# berimbau.net
KiCad netlist of a schematic drawn in EAGLE
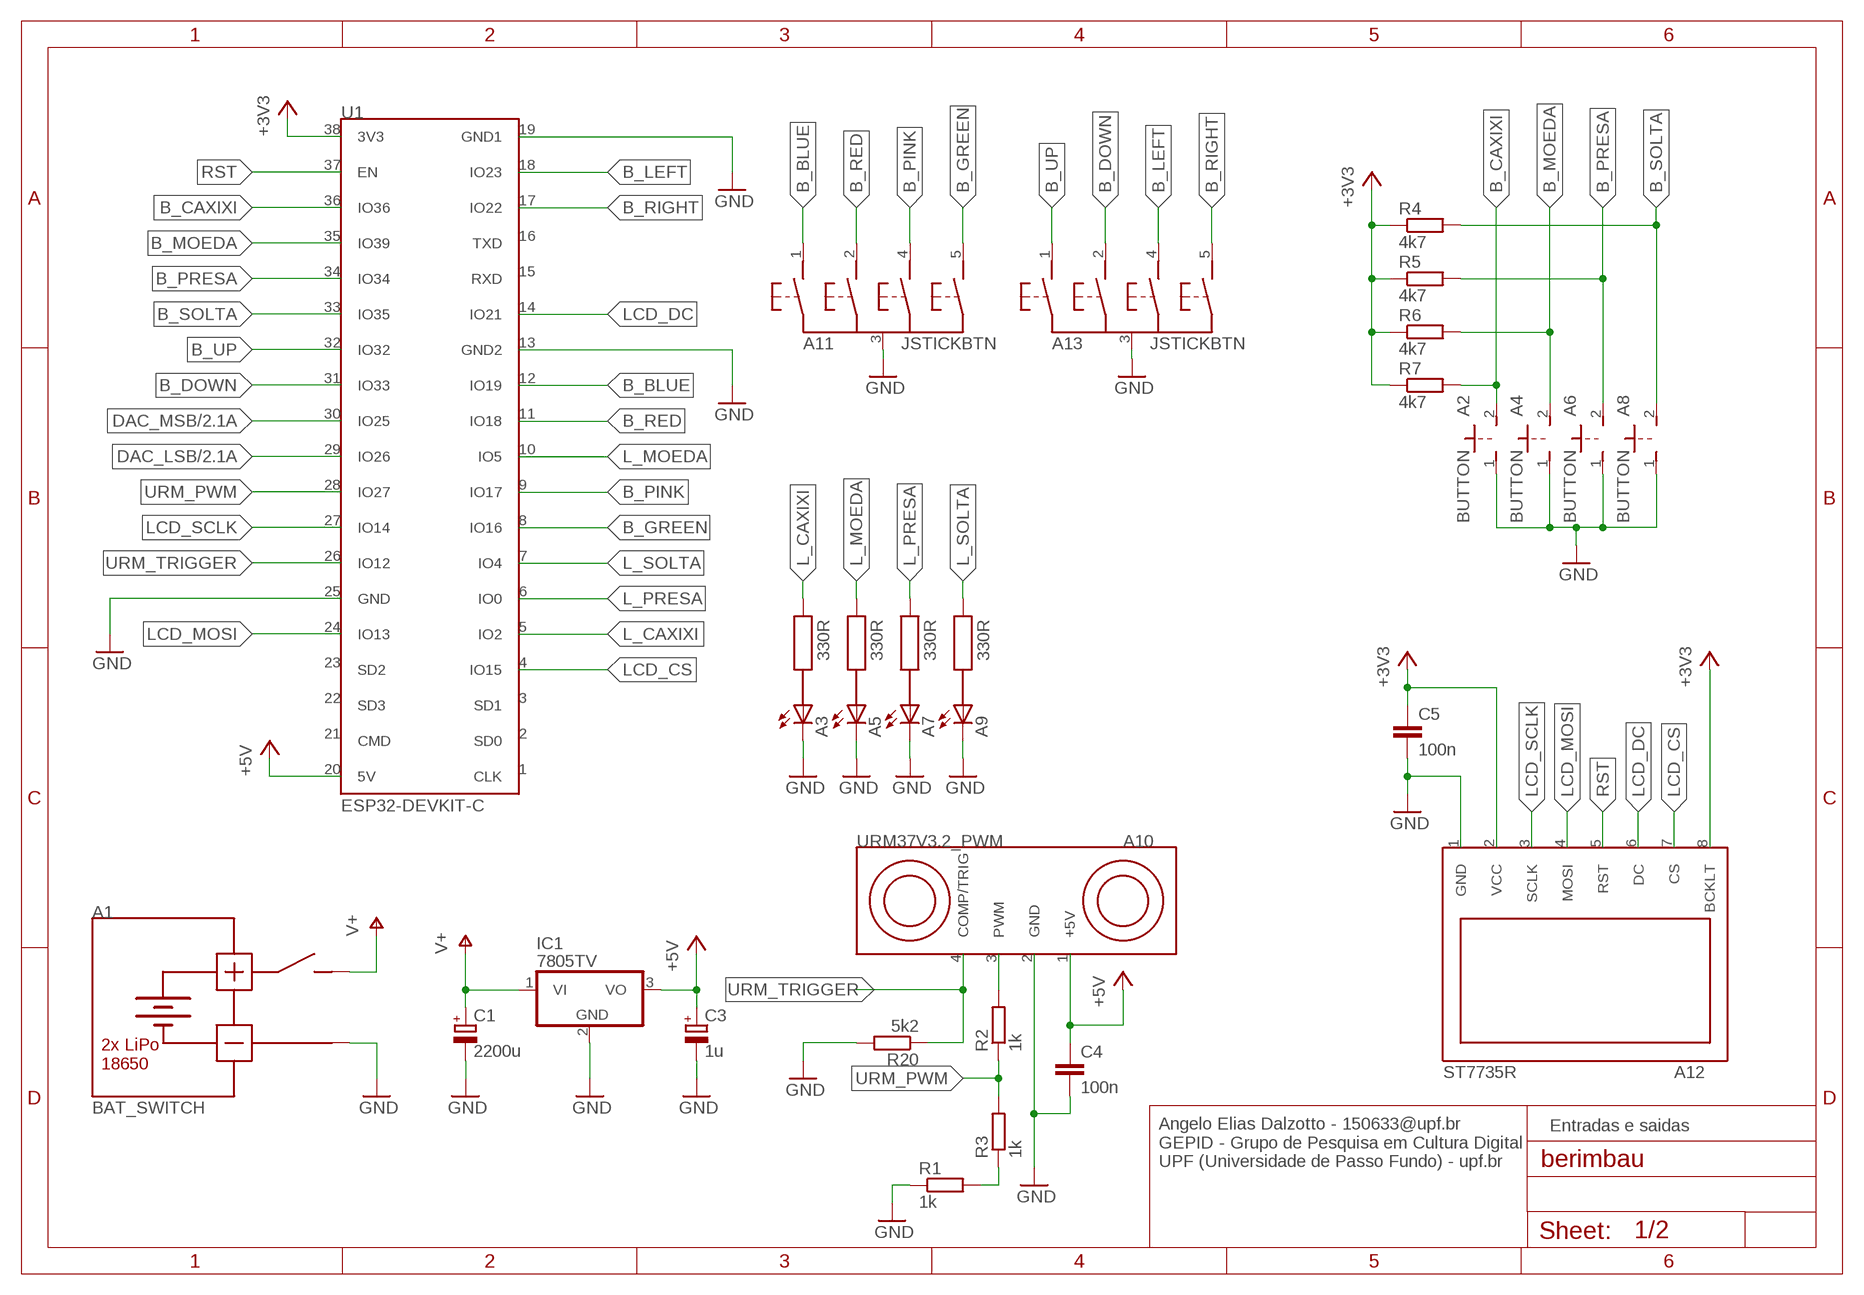
[diagram p0: schematic, sheet 1]
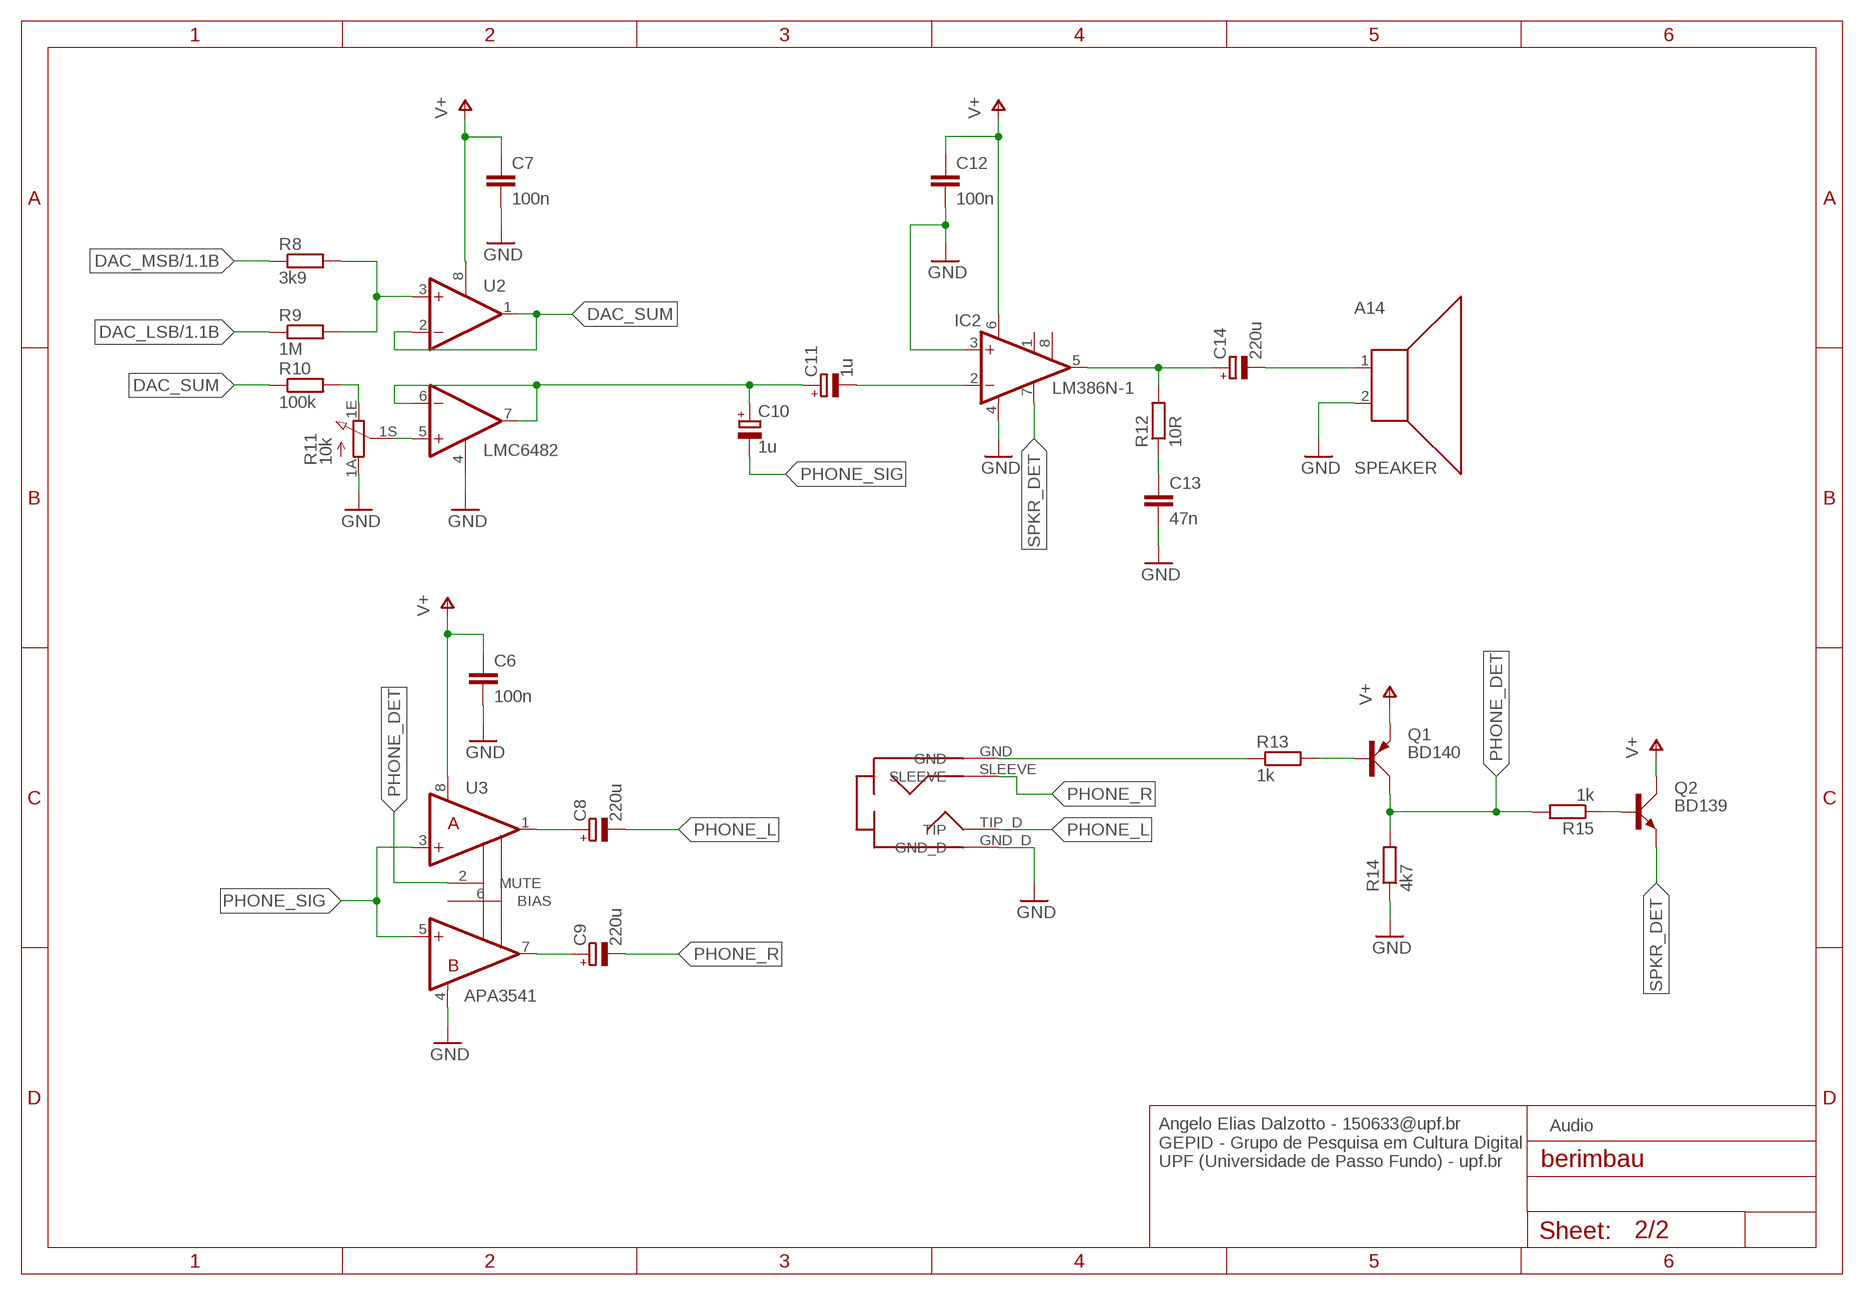
[diagram p1: schematic, sheet 2]

(export (version "E")
  (design (tool "Eeschema 10.0.6"))
  (components
    (comp (ref "A1")
      (value "BAT_SWITCH")
      (footprint "eagle-import:1X02")
      (libsource (lib "eagle-import") (part "BAT_SWITCH"))
    )
    (comp (ref "A2")
      (value "BUTTON")
      (footprint "eagle-import:1X02")
      (libsource (lib "eagle-import") (part "BUTTON"))
    )
    (comp (ref "A3")
      (value "LED")
      (footprint "eagle-import:1X02")
      (libsource (lib "eagle-import") (part "LED"))
    )
    (comp (ref "A4")
      (value "BUTTON")
      (footprint "eagle-import:1X02")
      (libsource (lib "eagle-import") (part "BUTTON"))
    )
    (comp (ref "A5")
      (value "LED")
      (footprint "eagle-import:1X02")
      (libsource (lib "eagle-import") (part "LED"))
    )
    (comp (ref "A6")
      (value "BUTTON")
      (footprint "eagle-import:1X02")
      (libsource (lib "eagle-import") (part "BUTTON"))
    )
    (comp (ref "A7")
      (value "LED")
      (footprint "eagle-import:1X02")
      (libsource (lib "eagle-import") (part "LED"))
    )
    (comp (ref "A8")
      (value "BUTTON")
      (footprint "eagle-import:1X02")
      (libsource (lib "eagle-import") (part "BUTTON"))
    )
    (comp (ref "A9")
      (value "LED")
      (footprint "eagle-import:1X02")
      (libsource (lib "eagle-import") (part "LED"))
    )
    (comp (ref "A10")
      (value "URM37V3.2_PWM")
      (footprint "eagle-import:1X04")
      (libsource (lib "eagle-import") (part "URM37V3.2_PWM"))
    )
    (comp (ref "A11")
      (value "JSTICKBTN")
      (footprint "eagle-import:1X05")
      (libsource (lib "eagle-import") (part "JSTICKBTN"))
    )
    (comp (ref "A12")
      (value "ST7735R")
      (footprint "eagle-import:1X08")
      (libsource (lib "eagle-import") (part "ST7735R"))
    )
    (comp (ref "A13")
      (value "JSTICKBTN")
      (footprint "eagle-import:1X05")
      (libsource (lib "eagle-import") (part "JSTICKBTN"))
    )
    (comp (ref "C1")
      (value "2200u")
      (footprint "eagle-import:E3,5-10")
      (libsource (lib "eagle-import") (part "CPOL-EUE3.5-10"))
    )
    (comp (ref "C3")
      (value "1u")
      (footprint "eagle-import:E2-5")
      (libsource (lib "eagle-import") (part "CPOL-EUE2-5"))
    )
    (comp (ref "C4")
      (value "100n")
      (footprint "eagle-import:C050-030X075")
      (libsource (lib "eagle-import") (part "C-EU050-030X075"))
    )
    (comp (ref "C5")
      (value "100n")
      (footprint "eagle-import:C050-030X075")
      (libsource (lib "eagle-import") (part "C-EU050-030X075"))
    )
    (comp (ref "IC1")
      (value "7805TV")
      (footprint "eagle-import:TO220V")
      (libsource (lib "eagle-import") (part "78TV05"))
    )
    (comp (ref "R1")
      (value "1k")
      (footprint "eagle-import:0207_10")
      (libsource (lib "eagle-import") (part "R-EU_0207/10"))
    )
    (comp (ref "R2")
      (value "1k")
      (footprint "eagle-import:0207_10")
      (libsource (lib "eagle-import") (part "R-EU_0207/10"))
    )
    (comp (ref "R3")
      (value "1k")
      (footprint "eagle-import:0207_10")
      (libsource (lib "eagle-import") (part "R-EU_0207/10"))
    )
    (comp (ref "R4")
      (value "4k7")
      (footprint "eagle-import:0207_10")
      (libsource (lib "eagle-import") (part "R-EU_0207/10"))
    )
    (comp (ref "R5")
      (value "4k7")
      (footprint "eagle-import:0207_10")
      (libsource (lib "eagle-import") (part "R-EU_0207/10"))
    )
    (comp (ref "R6")
      (value "4k7")
      (footprint "eagle-import:0207_10")
      (libsource (lib "eagle-import") (part "R-EU_0207/10"))
    )
    (comp (ref "R7")
      (value "4k7")
      (footprint "eagle-import:0207_10")
      (libsource (lib "eagle-import") (part "R-EU_0207/10"))
    )
    (comp (ref "R20")
      (value "5k2")
      (footprint "eagle-import:0207_10")
      (libsource (lib "eagle-import") (part "R-EU_0207/10"))
    )
    (comp (ref "U1")
      (value "ESP32-DEVKIT-C")
      (footprint "eagle-import:ESP32")
      (libsource (lib "eagle-import") (part "ESP32-DEVKIT-C"))
    )
    (comp (ref "A14")
      (value "SPEAKER")
      (footprint "eagle-import:1X02")
      (libsource (lib "eagle-import") (part "SPEAKER"))
    )
    (comp (ref "C6")
      (value "100n")
      (footprint "eagle-import:C050-030X075")
      (libsource (lib "eagle-import") (part "C-EU050-030X075"))
    )
    (comp (ref "C7")
      (value "100n")
      (footprint "eagle-import:C050-030X075")
      (libsource (lib "eagle-import") (part "C-EU050-030X075"))
    )
    (comp (ref "C8")
      (value "220u")
      (footprint "eagle-import:E2-5")
      (libsource (lib "eagle-import") (part "CPOL-EUE2-5"))
    )
    (comp (ref "C9")
      (value "220u")
      (footprint "eagle-import:E2-5")
      (libsource (lib "eagle-import") (part "CPOL-EUE2-5"))
    )
    (comp (ref "C10")
      (value "1u")
      (footprint "eagle-import:E2-5")
      (libsource (lib "eagle-import") (part "CPOL-EUE2-5"))
    )
    (comp (ref "C11")
      (value "1u")
      (footprint "eagle-import:E2-5")
      (libsource (lib "eagle-import") (part "CPOL-EUE2-5"))
    )
    (comp (ref "C12")
      (value "100n")
      (footprint "eagle-import:C050-030X075")
      (libsource (lib "eagle-import") (part "C-EU050-030X075"))
    )
    (comp (ref "C13")
      (value "47n")
      (footprint "eagle-import:C050-030X075")
      (libsource (lib "eagle-import") (part "C-EU050-030X075"))
    )
    (comp (ref "C14")
      (value "220u")
      (footprint "eagle-import:E3,5-10")
      (libsource (lib "eagle-import") (part "CPOL-EUE3.5-10"))
    )
    (comp (ref "IC2")
      (value "LM386N-1")
      (footprint "eagle-import:DIL08")
      (libsource (lib "eagle-import") (part "LM386?-N1"))
    )
    (comp (ref "J1")
      (value "P2_RPI")
      (footprint "eagle-import:P2_RASPI")
      (libsource (lib "eagle-import") (part "P2_RPI"))
    )
    (comp (ref "Q1")
      (value "BD140")
      (footprint "eagle-import:TO126AV")
      (libsource (lib "eagle-import") (part "BD140"))
    )
    (comp (ref "Q2")
      (value "BD139")
      (footprint "eagle-import:TO126AV")
      (libsource (lib "eagle-import") (part "BD139"))
    )
    (comp (ref "R8")
      (value "3k9")
      (footprint "eagle-import:0207_10")
      (libsource (lib "eagle-import") (part "R-EU_0207/10"))
    )
    (comp (ref "R9")
      (value "1M")
      (footprint "eagle-import:0207_10")
      (libsource (lib "eagle-import") (part "R-EU_0207/10"))
    )
    (comp (ref "R10")
      (value "100k")
      (footprint "eagle-import:0207_10")
      (libsource (lib "eagle-import") (part "R-EU_0207/10"))
    )
    (comp (ref "R11")
      (value "10k")
      (footprint "eagle-import:PC16S")
      (libsource (lib "eagle-import") (part "POT_SMALL"))
    )
    (comp (ref "R12")
      (value "10R")
      (footprint "eagle-import:0207_10")
      (libsource (lib "eagle-import") (part "R-EU_0207/10"))
    )
    (comp (ref "R13")
      (value "1k")
      (footprint "eagle-import:0207_10")
      (libsource (lib "eagle-import") (part "R-EU_0207/10"))
    )
    (comp (ref "R14")
      (value "4k7")
      (footprint "eagle-import:0207_10")
      (libsource (lib "eagle-import") (part "R-EU_0207/10"))
    )
    (comp (ref "R15")
      (value "1k")
      (footprint "eagle-import:0207_10")
      (libsource (lib "eagle-import") (part "R-EU_0207/10"))
    )
    (comp (ref "U2")
      (value "LMC6482")
      (footprint "eagle-import:DIL08")
      (libsource (lib "eagle-import") (part "LMC6482"))
    )
    (comp (ref "U3")
      (value "APA3541")
      (footprint "eagle-import:DIL08")
      (libsource (lib "eagle-import") (part "APA3541"))
    )
  )
  (nets
    (net (code "1") (name "+3V3") (class "Default")
      (node (ref "A12") (pin "2") (pinfunction "VCC_2") (pintype "power_in"))
      (node (ref "A12") (pin "8") (pinfunction "BCKLT_8") (pintype "input"))
      (node (ref "C5") (pin "1") (pinfunction "1_1") (pintype "passive"))
      (node (ref "R4") (pin "1") (pinfunction "1_1") (pintype "passive"))
      (node (ref "R5") (pin "1") (pinfunction "1_1") (pintype "passive"))
      (node (ref "R6") (pin "1") (pinfunction "1_1") (pintype "passive"))
      (node (ref "R7") (pin "1") (pinfunction "1_1") (pintype "passive"))
      (node (ref "U1") (pin "38") (pinfunction "3V3_38") (pintype "power_in"))
    )
    (net (code "2") (name "+5V") (class "Default")
      (node (ref "A10") (pin "1") (pinfunction "+5V_1") (pintype "power_in"))
      (node (ref "C3") (pin "+") (pinfunction "+_+") (pintype "passive"))
      (node (ref "C4") (pin "1") (pinfunction "1_1") (pintype "passive"))
      (node (ref "IC1") (pin "3") (pinfunction "VO_3") (pintype "passive"))
      (node (ref "U1") (pin "20") (pinfunction "5V_20") (pintype "power_in"))
    )
    (net (code "3") (name "B_BLUE") (class "Default")
      (node (ref "A11") (pin "1") (pinfunction "B1_1") (pintype "passive"))
      (node (ref "U1") (pin "12") (pinfunction "IO19_12") (pintype "bidirectional"))
    )
    (net (code "4") (name "B_CAXIXI") (class "Default")
      (node (ref "A2") (pin "2") (pinfunction "S_2") (pintype "passive"))
      (node (ref "R7") (pin "2") (pinfunction "2_2") (pintype "passive"))
      (node (ref "U1") (pin "36") (pinfunction "IO36_36") (pintype "input"))
    )
    (net (code "5") (name "B_DOWN") (class "Default")
      (node (ref "A13") (pin "2") (pinfunction "B2_2") (pintype "passive"))
      (node (ref "U1") (pin "31") (pinfunction "IO33_31") (pintype "bidirectional"))
    )
    (net (code "6") (name "B_GREEN") (class "Default")
      (node (ref "A11") (pin "5") (pinfunction "B4_5") (pintype "passive"))
      (node (ref "U1") (pin "8") (pinfunction "IO16_8") (pintype "bidirectional"))
    )
    (net (code "7") (name "B_LEFT") (class "Default")
      (node (ref "A13") (pin "4") (pinfunction "B3_4") (pintype "passive"))
      (node (ref "U1") (pin "18") (pinfunction "IO23_18") (pintype "bidirectional"))
    )
    (net (code "8") (name "B_MOEDA") (class "Default")
      (node (ref "A4") (pin "2") (pinfunction "S_2") (pintype "passive"))
      (node (ref "R6") (pin "2") (pinfunction "2_2") (pintype "passive"))
      (node (ref "U1") (pin "35") (pinfunction "IO39_35") (pintype "input"))
    )
    (net (code "9") (name "B_PINK") (class "Default")
      (node (ref "A11") (pin "4") (pinfunction "B3_4") (pintype "passive"))
      (node (ref "U1") (pin "9") (pinfunction "IO17_9") (pintype "bidirectional"))
    )
    (net (code "10") (name "B_PRESA") (class "Default")
      (node (ref "A6") (pin "2") (pinfunction "S_2") (pintype "passive"))
      (node (ref "R5") (pin "2") (pinfunction "2_2") (pintype "passive"))
      (node (ref "U1") (pin "34") (pinfunction "IO34_34") (pintype "input"))
    )
    (net (code "11") (name "B_RED") (class "Default")
      (node (ref "A11") (pin "2") (pinfunction "B2_2") (pintype "passive"))
      (node (ref "U1") (pin "11") (pinfunction "IO18_11") (pintype "bidirectional"))
    )
    (net (code "12") (name "B_RIGHT") (class "Default")
      (node (ref "A13") (pin "5") (pinfunction "B4_5") (pintype "passive"))
      (node (ref "U1") (pin "17") (pinfunction "IO22_17") (pintype "bidirectional"))
    )
    (net (code "13") (name "B_SOLTA") (class "Default")
      (node (ref "A8") (pin "2") (pinfunction "S_2") (pintype "passive"))
      (node (ref "R4") (pin "2") (pinfunction "2_2") (pintype "passive"))
      (node (ref "U1") (pin "33") (pinfunction "IO35_33") (pintype "input"))
    )
    (net (code "14") (name "B_UP") (class "Default")
      (node (ref "A13") (pin "1") (pinfunction "B1_1") (pintype "passive"))
      (node (ref "U1") (pin "32") (pinfunction "IO32_32") (pintype "bidirectional"))
    )
    (net (code "15") (name "DAC_LSB") (class "Default")
      (node (ref "R9") (pin "1") (pinfunction "1_1") (pintype "passive"))
      (node (ref "U1") (pin "29") (pinfunction "IO26_29") (pintype "bidirectional"))
    )
    (net (code "16") (name "DAC_MSB") (class "Default")
      (node (ref "R8") (pin "1") (pinfunction "1_1") (pintype "passive"))
      (node (ref "U1") (pin "30") (pinfunction "IO25_30") (pintype "bidirectional"))
    )
    (net (code "17") (name "DAC_SUM") (class "Default")
      (node (ref "R10") (pin "1") (pinfunction "1_1") (pintype "passive"))
      (node (ref "U2") (pin "1") (pinfunction "OUT_A_1") (pintype "output"))
      (node (ref "U2") (pin "2") (pinfunction "-IN_A_2") (pintype "input"))
    )
    (net (code "18") (name "GND") (class "Default")
      (node (ref "A1") (pin "2") (pinfunction "-_2") (pintype "power_in"))
      (node (ref "A10") (pin "2") (pinfunction "GND_2") (pintype "power_in"))
      (node (ref "A11") (pin "3") (pinfunction "COM_3") (pintype "passive"))
      (node (ref "A12") (pin "1") (pinfunction "GND_1") (pintype "power_in"))
      (node (ref "A13") (pin "3") (pinfunction "COM_3") (pintype "passive"))
      (node (ref "A14") (pin "2") (pinfunction "-_2") (pintype "passive"))
      (node (ref "A2") (pin "1") (pinfunction "P_1") (pintype "passive"))
      (node (ref "A3") (pin "2") (pinfunction "C_2") (pintype "passive"))
      (node (ref "A4") (pin "1") (pinfunction "P_1") (pintype "passive"))
      (node (ref "A5") (pin "2") (pinfunction "C_2") (pintype "passive"))
      (node (ref "A6") (pin "1") (pinfunction "P_1") (pintype "passive"))
      (node (ref "A7") (pin "2") (pinfunction "C_2") (pintype "passive"))
      (node (ref "A8") (pin "1") (pinfunction "P_1") (pintype "passive"))
      (node (ref "A9") (pin "2") (pinfunction "C_2") (pintype "passive"))
      (node (ref "C1") (pin "-") (pinfunction "-_-") (pintype "passive"))
      (node (ref "C12") (pin "2") (pinfunction "2_2") (pintype "passive"))
      (node (ref "C13") (pin "2") (pinfunction "2_2") (pintype "passive"))
      (node (ref "C3") (pin "-") (pinfunction "-_-") (pintype "passive"))
      (node (ref "C4") (pin "2") (pinfunction "2_2") (pintype "passive"))
      (node (ref "C5") (pin "2") (pinfunction "2_2") (pintype "passive"))
      (node (ref "C6") (pin "2") (pinfunction "2_2") (pintype "passive"))
      (node (ref "C7") (pin "2") (pinfunction "2_2") (pintype "passive"))
      (node (ref "IC1") (pin "2") (pinfunction "GND_2") (pintype "passive"))
      (node (ref "IC2") (pin "3") (pinfunction "+IN_3") (pintype "input"))
      (node (ref "IC2") (pin "4") (pinfunction "GND_4") (pintype "power_in"))
      (node (ref "J1") (pin "GND_D") (pinfunction "GND_D_GND_D") (pintype "bidirectional"))
      (node (ref "R1") (pin "1") (pinfunction "1_1") (pintype "passive"))
      (node (ref "R11") (pin "1A") (pinfunction "A_1A") (pintype "passive"))
      (node (ref "R14") (pin "1") (pinfunction "1_1") (pintype "passive"))
      (node (ref "R20") (pin "2") (pinfunction "2_2") (pintype "passive"))
      (node (ref "U1") (pin "13") (pinfunction "GND2_13") (pintype "power_in"))
      (node (ref "U1") (pin "19") (pinfunction "GND1_19") (pintype "power_in"))
      (node (ref "U1") (pin "25") (pinfunction "GND_25") (pintype "power_in"))
      (node (ref "U2") (pin "4") (pinfunction "V-_4") (pintype "power_in"))
      (node (ref "U3") (pin "4") (pinfunction "GND_4") (pintype "power_in"))
    )
    (net (code "19") (name "LCD_CS") (class "Default")
      (node (ref "A12") (pin "7") (pinfunction "CS_7") (pintype "input"))
      (node (ref "U1") (pin "4") (pinfunction "IO15_4") (pintype "output"))
    )
    (net (code "20") (name "LCD_DC") (class "Default")
      (node (ref "A12") (pin "6") (pinfunction "DC_6") (pintype "input"))
      (node (ref "U1") (pin "14") (pinfunction "IO21_14") (pintype "bidirectional"))
    )
    (net (code "21") (name "LCD_MOSI") (class "Default")
      (node (ref "A12") (pin "4") (pinfunction "MOSI_4") (pintype "input"))
      (node (ref "U1") (pin "24") (pinfunction "IO13_24") (pintype "bidirectional"))
    )
    (net (code "22") (name "LCD_SCLK") (class "Default")
      (node (ref "A12") (pin "3") (pinfunction "SCLK_3") (pintype "input"))
      (node (ref "U1") (pin "27") (pinfunction "IO14_27") (pintype "bidirectional"))
    )
    (net (code "23") (name "L_CAXIXI") (class "Default")
      (node (ref "A3") (pin "1") (pinfunction "A_1") (pintype "passive"))
      (node (ref "U1") (pin "5") (pinfunction "IO2_5") (pintype "output"))
    )
    (net (code "24") (name "L_MOEDA") (class "Default")
      (node (ref "A5") (pin "1") (pinfunction "A_1") (pintype "passive"))
      (node (ref "U1") (pin "10") (pinfunction "IO5_10") (pintype "output"))
    )
    (net (code "25") (name "L_PRESA") (class "Default")
      (node (ref "A7") (pin "1") (pinfunction "A_1") (pintype "passive"))
      (node (ref "U1") (pin "6") (pinfunction "IO0_6") (pintype "output"))
    )
    (net (code "26") (name "L_SOLTA") (class "Default")
      (node (ref "A9") (pin "1") (pinfunction "A_1") (pintype "passive"))
      (node (ref "U1") (pin "7") (pinfunction "IO4_7") (pintype "output"))
    )
    (net (code "27") (name "Net-(A10-PWM)") (class "Default")
      (node (ref "A10") (pin "3") (pinfunction "PWM_3") (pintype "output"))
      (node (ref "R2") (pin "2") (pinfunction "2_2") (pintype "passive"))
    )
    (net (code "28") (name "Net-(A14-+)") (class "Default")
      (node (ref "A14") (pin "1") (pinfunction "+_1") (pintype "passive"))
      (node (ref "C14") (pin "-") (pinfunction "-_-") (pintype "passive"))
    )
    (net (code "29") (name "Net-(C13-Pad1)") (class "Default")
      (node (ref "C13") (pin "1") (pinfunction "1_1") (pintype "passive"))
      (node (ref "R12") (pin "1") (pinfunction "1_1") (pintype "passive"))
    )
    (net (code "30") (name "Net-(IC2--IN)") (class "Default")
      (node (ref "C11") (pin "-") (pinfunction "-_-") (pintype "passive"))
      (node (ref "IC2") (pin "2") (pinfunction "-IN_2") (pintype "input"))
    )
    (net (code "31") (name "Net-(IC2-OUT)") (class "Default")
      (node (ref "C14") (pin "+") (pinfunction "+_+") (pintype "passive"))
      (node (ref "IC2") (pin "5") (pinfunction "OUT_5") (pintype "output"))
      (node (ref "R12") (pin "2") (pinfunction "2_2") (pintype "passive"))
    )
    (net (code "32") (name "Net-(J1-PadGND)") (class "Default")
      (node (ref "J1") (pin "GND") (pinfunction "GND_GND") (pintype "bidirectional"))
      (node (ref "R13") (pin "1") (pinfunction "1_1") (pintype "passive"))
    )
    (net (code "33") (name "Net-(Q1-PadB)") (class "Default")
      (node (ref "Q1") (pin "B") (pinfunction "B_B") (pintype "passive"))
      (node (ref "R13") (pin "2") (pinfunction "2_2") (pintype "passive"))
    )
    (net (code "34") (name "Net-(Q2-PadB)") (class "Default")
      (node (ref "Q2") (pin "B") (pinfunction "B_B") (pintype "passive"))
      (node (ref "R15") (pin "1") (pinfunction "1_1") (pintype "passive"))
    )
    (net (code "35") (name "Net-(R1-Pad2)") (class "Default")
      (node (ref "R1") (pin "2") (pinfunction "2_2") (pintype "passive"))
      (node (ref "R3") (pin "1") (pinfunction "1_1") (pintype "passive"))
    )
    (net (code "36") (name "Net-(R11-E)") (class "Default")
      (node (ref "R10") (pin "2") (pinfunction "2_2") (pintype "passive"))
      (node (ref "R11") (pin "1E") (pinfunction "E_1E") (pintype "passive"))
    )
    (net (code "37") (name "Net-(R11-S)") (class "Default")
      (node (ref "R11") (pin "1S") (pinfunction "S_1S") (pintype "passive"))
      (node (ref "U2") (pin "5") (pinfunction "+IN_B_5") (pintype "input"))
    )
    (net (code "38") (name "Net-(U2-+IN_A)") (class "Default")
      (node (ref "R8") (pin "2") (pinfunction "2_2") (pintype "passive"))
      (node (ref "R9") (pin "2") (pinfunction "2_2") (pintype "passive"))
      (node (ref "U2") (pin "3") (pinfunction "+IN_A_3") (pintype "input"))
    )
    (net (code "39") (name "Net-(U2--IN_B)") (class "Default")
      (node (ref "C10") (pin "+") (pinfunction "+_+") (pintype "passive"))
      (node (ref "C11") (pin "+") (pinfunction "+_+") (pintype "passive"))
      (node (ref "U2") (pin "6") (pinfunction "-IN_B_6") (pintype "input"))
      (node (ref "U2") (pin "7") (pinfunction "OUT_B_7") (pintype "output"))
    )
    (net (code "40") (name "Net-(U3-OUT_A)") (class "Default")
      (node (ref "C8") (pin "+") (pinfunction "+_+") (pintype "passive"))
      (node (ref "U3") (pin "1") (pinfunction "OUT_A_1") (pintype "output"))
    )
    (net (code "41") (name "Net-(U3-OUT_B)") (class "Default")
      (node (ref "C9") (pin "+") (pinfunction "+_+") (pintype "passive"))
      (node (ref "U3") (pin "7") (pinfunction "OUT_B_7") (pintype "output"))
    )
    (net (code "42") (name "PHONE_DET") (class "Default")
      (node (ref "Q1") (pin "C") (pinfunction "C_C") (pintype "passive"))
      (node (ref "R14") (pin "2") (pinfunction "2_2") (pintype "passive"))
      (node (ref "R15") (pin "2") (pinfunction "2_2") (pintype "passive"))
      (node (ref "U3") (pin "2") (pinfunction "MUTE_2") (pintype "input"))
    )
    (net (code "43") (name "PHONE_L") (class "Default")
      (node (ref "C8") (pin "-") (pinfunction "-_-") (pintype "passive"))
      (node (ref "J1") (pin "TIP_D") (pinfunction "TIP_TIP_D") (pintype "bidirectional"))
    )
    (net (code "44") (name "PHONE_R") (class "Default")
      (node (ref "C9") (pin "-") (pinfunction "-_-") (pintype "passive"))
      (node (ref "J1") (pin "SLEEVE") (pinfunction "SLEEVE_SLEEVE") (pintype "bidirectional"))
    )
    (net (code "45") (name "PHONE_SIG") (class "Default")
      (node (ref "C10") (pin "-") (pinfunction "-_-") (pintype "passive"))
      (node (ref "U3") (pin "3") (pinfunction "+IN_A_3") (pintype "input"))
      (node (ref "U3") (pin "5") (pinfunction "+IN_B_5") (pintype "input"))
    )
    (net (code "46") (name "RST") (class "Default")
      (node (ref "A12") (pin "5") (pinfunction "RST_5") (pintype "input"))
      (node (ref "U1") (pin "37") (pinfunction "EN_37") (pintype "bidirectional"))
    )
    (net (code "47") (name "SPKR_DET") (class "Default")
      (node (ref "IC2") (pin "7") (pinfunction "BYPASS_7") (pintype "passive"))
      (node (ref "Q2") (pin "E") (pinfunction "E_E") (pintype "passive"))
    )
    (net (code "48") (name "URM_PWM") (class "Default")
      (node (ref "R2") (pin "1") (pinfunction "1_1") (pintype "passive"))
      (node (ref "R3") (pin "2") (pinfunction "2_2") (pintype "passive"))
      (node (ref "U1") (pin "28") (pinfunction "IO27_28") (pintype "bidirectional"))
    )
    (net (code "49") (name "URM_TRIGGER") (class "Default")
      (node (ref "A10") (pin "4") (pinfunction "COMP/TRIG_4") (pintype "input"))
      (node (ref "R20") (pin "1") (pinfunction "1_1") (pintype "passive"))
      (node (ref "U1") (pin "26") (pinfunction "IO12_26") (pintype "output"))
    )
    (net (code "50") (name "V+") (class "Default")
      (node (ref "A1") (pin "1") (pinfunction "+_1") (pintype "power_in"))
      (node (ref "C1") (pin "+") (pinfunction "+_+") (pintype "passive"))
      (node (ref "C12") (pin "1") (pinfunction "1_1") (pintype "passive"))
      (node (ref "C6") (pin "1") (pinfunction "1_1") (pintype "passive"))
      (node (ref "C7") (pin "1") (pinfunction "1_1") (pintype "passive"))
      (node (ref "IC1") (pin "1") (pinfunction "VI_1") (pintype "input"))
      (node (ref "IC2") (pin "6") (pinfunction "VS_6") (pintype "power_in"))
      (node (ref "Q1") (pin "E") (pinfunction "E_E") (pintype "passive"))
      (node (ref "Q2") (pin "C") (pinfunction "C_C") (pintype "passive"))
      (node (ref "U2") (pin "8") (pinfunction "V+_8") (pintype "power_in"))
      (node (ref "U3") (pin "8") (pinfunction "VS1_8") (pintype "power_in"))
    )
    (net (code "51") (name "unconnected-(IC2-GAIN-Pad1)") (class "Default")
      (node (ref "IC2") (pin "1") (pinfunction "GAIN_1") (pintype "passive"))
    )
    (net (code "52") (name "unconnected-(IC2-GAIN-Pad8)") (class "Default")
      (node (ref "IC2") (pin "8") (pinfunction "GAIN_8") (pintype "passive"))
    )
    (net (code "53") (name "unconnected-(U1-CLK-Pad1)") (class "Default")
      (node (ref "U1") (pin "1") (pinfunction "CLK_1") (pintype "no_connect"))
    )
    (net (code "54") (name "unconnected-(U1-CMD-Pad21)") (class "Default")
      (node (ref "U1") (pin "21") (pinfunction "CMD_21") (pintype "no_connect"))
    )
    (net (code "55") (name "unconnected-(U1-RXD-Pad15)") (class "Default")
      (node (ref "U1") (pin "15") (pinfunction "RXD_15") (pintype "no_connect"))
    )
    (net (code "56") (name "unconnected-(U1-SD0-Pad2)") (class "Default")
      (node (ref "U1") (pin "2") (pinfunction "SD0_2") (pintype "no_connect"))
    )
    (net (code "57") (name "unconnected-(U1-SD1-Pad3)") (class "Default")
      (node (ref "U1") (pin "3") (pinfunction "SD1_3") (pintype "no_connect"))
    )
    (net (code "58") (name "unconnected-(U1-SD2-Pad23)") (class "Default")
      (node (ref "U1") (pin "23") (pinfunction "SD2_23") (pintype "no_connect"))
    )
    (net (code "59") (name "unconnected-(U1-SD3-Pad22)") (class "Default")
      (node (ref "U1") (pin "22") (pinfunction "SD3_22") (pintype "no_connect"))
    )
    (net (code "60") (name "unconnected-(U1-TXD-Pad16)") (class "Default")
      (node (ref "U1") (pin "16") (pinfunction "TXD_16") (pintype "no_connect"))
    )
    (net (code "61") (name "unconnected-(U3-BIAS-Pad6)") (class "Default")
      (node (ref "U3") (pin "6") (pinfunction "BIAS_6") (pintype "passive"))
    )
  )
)
